# led-er-v2.net
KiCad netlist of a schematic drawn in EAGLE
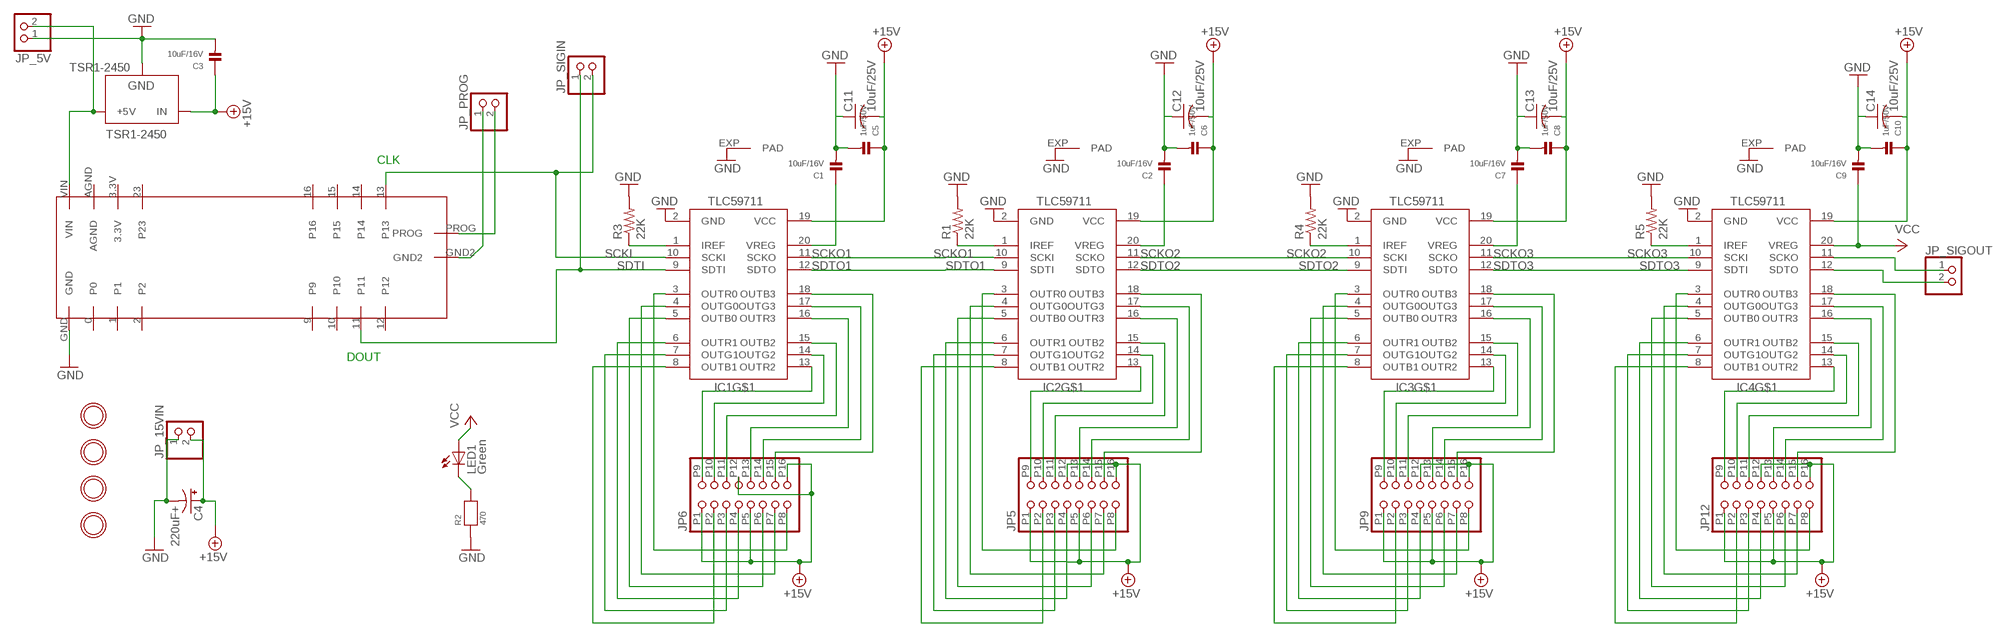
[diagram p0: schematic, sheet 1]

(export (version "E")
  (design (tool "Eeschema 10.0.6"))
  (components
    (comp (ref "C1")
      (value "10uF/16V")
      (footprint "eagle-import:0805")
      (libsource (lib "eagle-import") (part "CAP_CERAMIC0805"))
    )
    (comp (ref "C2")
      (value "10uF/16V")
      (footprint "eagle-import:0805")
      (libsource (lib "eagle-import") (part "CAP_CERAMIC0805"))
    )
    (comp (ref "C3")
      (value "10uF/16V")
      (footprint "eagle-import:0805")
      (libsource (lib "eagle-import") (part "CAP_CERAMIC0805"))
    )
    (comp (ref "C4")
      (value "220uF+")
      (footprint "eagle-import:E5-8,5")
      (libsource (lib "eagle-import") (part "CPOL-USE5-8.5"))
    )
    (comp (ref "C5")
      (value "1uF/50V")
      (footprint "eagle-import:0805")
      (libsource (lib "eagle-import") (part "CAP_CERAMIC0805"))
    )
    (comp (ref "C6")
      (value "1uF/50V")
      (footprint "eagle-import:0805")
      (libsource (lib "eagle-import") (part "CAP_CERAMIC0805"))
    )
    (comp (ref "C7")
      (value "10uF/16V")
      (footprint "eagle-import:0805")
      (libsource (lib "eagle-import") (part "CAP_CERAMIC0805"))
    )
    (comp (ref "C8")
      (value "1uF/50V")
      (footprint "eagle-import:0805")
      (libsource (lib "eagle-import") (part "CAP_CERAMIC0805"))
    )
    (comp (ref "C9")
      (value "10uF/16V")
      (footprint "eagle-import:0805")
      (libsource (lib "eagle-import") (part "CAP_CERAMIC0805"))
    )
    (comp (ref "C10")
      (value "1uF/50V")
      (footprint "eagle-import:0805")
      (libsource (lib "eagle-import") (part "CAP_CERAMIC0805"))
    )
    (comp (ref "C11")
      (value "10uF/25V")
      (footprint "eagle-import:C0805")
      (libsource (lib "eagle-import") (part "C-USC0805"))
    )
    (comp (ref "C12")
      (value "10uF/25V")
      (footprint "eagle-import:C0805")
      (libsource (lib "eagle-import") (part "C-USC0805"))
    )
    (comp (ref "C13")
      (value "10uF/25V")
      (footprint "eagle-import:C0805")
      (libsource (lib "eagle-import") (part "C-USC0805"))
    )
    (comp (ref "C14")
      (value "10uF/25V")
      (footprint "eagle-import:C0805")
      (libsource (lib "eagle-import") (part "C-USC0805"))
    )
    (comp (ref "IC1")
      (value "TLC59711")
      (footprint "eagle-import:HTSSOP20DAP")
      (libsource (lib "eagle-import") (part "TLC59711"))
    )
    (comp (ref "IC2")
      (value "TLC59711")
      (footprint "eagle-import:HTSSOP20DAP")
      (libsource (lib "eagle-import") (part "TLC59711"))
    )
    (comp (ref "IC3")
      (value "TLC59711")
      (footprint "eagle-import:HTSSOP20DAP")
      (libsource (lib "eagle-import") (part "TLC59711"))
    )
    (comp (ref "IC4")
      (value "TLC59711")
      (footprint "eagle-import:HTSSOP20DAP")
      (libsource (lib "eagle-import") (part "TLC59711"))
    )
    (comp (ref "JP5")
      (value "HEADER-2X8")
      (footprint "eagle-import:2X08")
      (libsource (lib "eagle-import") (part "HEADER-2X8"))
    )
    (comp (ref "JP6")
      (value "HEADER-2X8")
      (footprint "eagle-import:2X08")
      (libsource (lib "eagle-import") (part "HEADER-2X8"))
    )
    (comp (ref "JP9")
      (value "HEADER-2X8")
      (footprint "eagle-import:2X08")
      (libsource (lib "eagle-import") (part "HEADER-2X8"))
    )
    (comp (ref "JP12")
      (value "HEADER-2X8")
      (footprint "eagle-import:2X08")
      (libsource (lib "eagle-import") (part "HEADER-2X8"))
    )
    (comp (ref "JP_5V")
      (value "HEADER-1X2")
      (footprint "eagle-import:1X02_OVAL")
      (libsource (lib "eagle-import") (part "HEADER-1X2"))
    )
    (comp (ref "JP_15VIN")
      (value "HEADER-1X2")
      (footprint "eagle-import:1X02_OVAL")
      (libsource (lib "eagle-import") (part "HEADER-1X2"))
    )
    (comp (ref "JP_PROG")
      (value "HEADER-1X2")
      (footprint "eagle-import:1X02_OVAL")
      (libsource (lib "eagle-import") (part "HEADER-1X2"))
    )
    (comp (ref "JP_SIGIN")
      (value "HEADER-1X2")
      (footprint "eagle-import:1X02_OVAL")
      (libsource (lib "eagle-import") (part "HEADER-1X2"))
    )
    (comp (ref "JP_SIGOUT")
      (value "HEADER-1X2")
      (footprint "eagle-import:1X02_OVAL")
      (libsource (lib "eagle-import") (part "HEADER-1X2"))
    )
    (comp (ref "LED1")
      (value "Green")
      (footprint "eagle-import:CHIP-LED0805")
      (libsource (lib "eagle-import") (part "LEDCHIP-LED0805"))
    )
    (comp (ref "R1")
      (value "22K")
      (footprint "eagle-import:0805-THM-7")
      (libsource (lib "eagle-import") (part "R-US_FLIPFLOP7"))
    )
    (comp (ref "R2")
      (value "470")
      (footprint "eagle-import:0805")
      (libsource (lib "eagle-import") (part "RESISTOR0805"))
    )
    (comp (ref "R3")
      (value "22K")
      (footprint "eagle-import:0805-THM-7")
      (libsource (lib "eagle-import") (part "R-US_FLIPFLOP7"))
    )
    (comp (ref "R4")
      (value "22K")
      (footprint "eagle-import:0805-THM-7")
      (libsource (lib "eagle-import") (part "R-US_FLIPFLOP7"))
    )
    (comp (ref "R5")
      (value "22K")
      (footprint "eagle-import:0805-THM-7")
      (libsource (lib "eagle-import") (part "R-US_FLIPFLOP7"))
    )
    (comp (ref "TSR1-2450")
      (value "TSR1-2450")
      (footprint "eagle-import:TSR-1")
      (libsource (lib "eagle-import") (part "TSR1-2450"))
    )
    (comp (ref "U$1")
      (value "MOUNTINGHOLE")
      (footprint "eagle-import:MOUNTINGHOLE_3.0_PLATED")
      (libsource (lib "eagle-import") (part "MOUNTINGHOLE"))
    )
    (comp (ref "U$2")
      (value "MOUNTINGHOLE")
      (footprint "eagle-import:MOUNTINGHOLE_3.0_PLATED")
      (libsource (lib "eagle-import") (part "MOUNTINGHOLE"))
    )
    (comp (ref "U$3")
      (value "MOUNTINGHOLE")
      (footprint "eagle-import:MOUNTINGHOLE_3.0_PLATED")
      (libsource (lib "eagle-import") (part "MOUNTINGHOLE"))
    )
    (comp (ref "U$4")
      (value "MOUNTINGHOLE")
      (footprint "eagle-import:MOUNTINGHOLE_3.0_PLATED")
      (libsource (lib "eagle-import") (part "MOUNTINGHOLE"))
    )
    (comp (ref "U$5")
      (value "TEENSY_LEDER")
      (footprint "eagle-import:TEENSY_LEDER")
      (libsource (lib "eagle-import") (part "TEENSY_LEDER"))
    )
  )
  (nets
    (net (code "1") (name "+15V") (class "Default")
      (node (ref "C10") (pin "1") (pinfunction "P$1_1") (pintype "passive"))
      (node (ref "C11") (pin "2") (pinfunction "2_2") (pintype "passive"))
      (node (ref "C12") (pin "2") (pinfunction "2_2") (pintype "passive"))
      (node (ref "C13") (pin "2") (pinfunction "2_2") (pintype "passive"))
      (node (ref "C14") (pin "2") (pinfunction "2_2") (pintype "passive"))
      (node (ref "C3") (pin "1") (pinfunction "P$1_1") (pintype "passive"))
      (node (ref "C4") (pin "+") (pinfunction "+_+") (pintype "passive"))
      (node (ref "C5") (pin "1") (pinfunction "P$1_1") (pintype "passive"))
      (node (ref "C6") (pin "1") (pinfunction "P$1_1") (pintype "passive"))
      (node (ref "C8") (pin "1") (pinfunction "P$1_1") (pintype "passive"))
      (node (ref "IC1") (pin "19") (pinfunction "VCC_19") (pintype "power_in"))
      (node (ref "IC2") (pin "19") (pinfunction "VCC_19") (pintype "power_in"))
      (node (ref "IC3") (pin "19") (pinfunction "VCC_19") (pintype "power_in"))
      (node (ref "IC4") (pin "19") (pinfunction "VCC_19") (pintype "power_in"))
      (node (ref "JP12") (pin "P1") (pinfunction "P1_P1") (pintype "passive"))
      (node (ref "JP12") (pin "P12") (pinfunction "P12_P12") (pintype "passive"))
      (node (ref "JP12") (pin "P16") (pinfunction "P16_P16") (pintype "passive"))
      (node (ref "JP12") (pin "P5") (pinfunction "P5_P5") (pintype "passive"))
      (node (ref "JP5") (pin "P1") (pinfunction "P1_P1") (pintype "passive"))
      (node (ref "JP5") (pin "P12") (pinfunction "P12_P12") (pintype "passive"))
      (node (ref "JP5") (pin "P16") (pinfunction "P16_P16") (pintype "passive"))
      (node (ref "JP5") (pin "P5") (pinfunction "P5_P5") (pintype "passive"))
      (node (ref "JP6") (pin "P1") (pinfunction "P1_P1") (pintype "passive"))
      (node (ref "JP6") (pin "P12") (pinfunction "P12_P12") (pintype "passive"))
      (node (ref "JP6") (pin "P16") (pinfunction "P16_P16") (pintype "passive"))
      (node (ref "JP6") (pin "P5") (pinfunction "P5_P5") (pintype "passive"))
      (node (ref "JP9") (pin "P1") (pinfunction "P1_P1") (pintype "passive"))
      (node (ref "JP9") (pin "P12") (pinfunction "P12_P12") (pintype "passive"))
      (node (ref "JP9") (pin "P16") (pinfunction "P16_P16") (pintype "passive"))
      (node (ref "JP9") (pin "P5") (pinfunction "P5_P5") (pintype "passive"))
      (node (ref "JP_15VIN") (pin "2") (pinfunction "2_2") (pintype "passive"))
      (node (ref "TSR1-2450") (pin "1") (pinfunction "IN_1") (pintype "power_in"))
    )
    (net (code "2") (name "/SCKI") (class "Default")
      (node (ref "IC1") (pin "10") (pinfunction "SCKI_10") (pintype "input"))
      (node (ref "JP_SIGIN") (pin "2") (pinfunction "2_2") (pintype "passive"))
      (node (ref "U$5") (pin "13") (pinfunction "P13_13") (pintype "bidirectional"))
    )
    (net (code "3") (name "/SCKO1") (class "Default")
      (node (ref "IC1") (pin "11") (pinfunction "SCKO_11") (pintype "output"))
      (node (ref "IC2") (pin "10") (pinfunction "SCKI_10") (pintype "input"))
    )
    (net (code "4") (name "/SCKO2") (class "Default")
      (node (ref "IC2") (pin "11") (pinfunction "SCKO_11") (pintype "output"))
      (node (ref "IC3") (pin "10") (pinfunction "SCKI_10") (pintype "input"))
    )
    (net (code "5") (name "/SCKO3") (class "Default")
      (node (ref "IC3") (pin "11") (pinfunction "SCKO_11") (pintype "output"))
      (node (ref "IC4") (pin "10") (pinfunction "SCKI_10") (pintype "input"))
    )
    (net (code "6") (name "/SDTI") (class "Default")
      (node (ref "IC1") (pin "9") (pinfunction "SDTI_9") (pintype "input"))
      (node (ref "JP_SIGIN") (pin "1") (pinfunction "1_1") (pintype "passive"))
      (node (ref "U$5") (pin "11") (pinfunction "P11_11") (pintype "bidirectional"))
    )
    (net (code "7") (name "/SDTO1") (class "Default")
      (node (ref "IC1") (pin "12") (pinfunction "SDTO_12") (pintype "output"))
      (node (ref "IC2") (pin "9") (pinfunction "SDTI_9") (pintype "input"))
    )
    (net (code "8") (name "/SDTO2") (class "Default")
      (node (ref "IC2") (pin "12") (pinfunction "SDTO_12") (pintype "output"))
      (node (ref "IC3") (pin "9") (pinfunction "SDTI_9") (pintype "input"))
    )
    (net (code "9") (name "/SDTO3") (class "Default")
      (node (ref "IC3") (pin "12") (pinfunction "SDTO_12") (pintype "output"))
      (node (ref "IC4") (pin "9") (pinfunction "SDTI_9") (pintype "input"))
    )
    (net (code "10") (name "GND") (class "Default")
      (node (ref "C1") (pin "2") (pinfunction "P$2_2") (pintype "passive"))
      (node (ref "C10") (pin "2") (pinfunction "P$2_2") (pintype "passive"))
      (node (ref "C11") (pin "1") (pinfunction "1_1") (pintype "passive"))
      (node (ref "C12") (pin "1") (pinfunction "1_1") (pintype "passive"))
      (node (ref "C13") (pin "1") (pinfunction "1_1") (pintype "passive"))
      (node (ref "C14") (pin "1") (pinfunction "1_1") (pintype "passive"))
      (node (ref "C2") (pin "2") (pinfunction "P$2_2") (pintype "passive"))
      (node (ref "C3") (pin "2") (pinfunction "P$2_2") (pintype "passive"))
      (node (ref "C4") (pin "-") (pinfunction "-_-") (pintype "passive"))
      (node (ref "C5") (pin "2") (pinfunction "P$2_2") (pintype "passive"))
      (node (ref "C6") (pin "2") (pinfunction "P$2_2") (pintype "passive"))
      (node (ref "C7") (pin "2") (pinfunction "P$2_2") (pintype "passive"))
      (node (ref "C8") (pin "2") (pinfunction "P$2_2") (pintype "passive"))
      (node (ref "C9") (pin "2") (pinfunction "P$2_2") (pintype "passive"))
      (node (ref "IC1") (pin "2") (pinfunction "GND_2") (pintype "power_in"))
      (node (ref "IC1") (pin "EXP") (pinfunction "PAD_EXP") (pintype "passive"))
      (node (ref "IC2") (pin "2") (pinfunction "GND_2") (pintype "power_in"))
      (node (ref "IC2") (pin "EXP") (pinfunction "PAD_EXP") (pintype "passive"))
      (node (ref "IC3") (pin "2") (pinfunction "GND_2") (pintype "power_in"))
      (node (ref "IC3") (pin "EXP") (pinfunction "PAD_EXP") (pintype "passive"))
      (node (ref "IC4") (pin "2") (pinfunction "GND_2") (pintype "power_in"))
      (node (ref "IC4") (pin "EXP") (pinfunction "PAD_EXP") (pintype "passive"))
      (node (ref "JP_15VIN") (pin "1") (pinfunction "1_1") (pintype "passive"))
      (node (ref "JP_5V") (pin "1") (pinfunction "1_1") (pintype "passive"))
      (node (ref "R1") (pin "2") (pinfunction "2_2") (pintype "passive"))
      (node (ref "R2") (pin "1") (pinfunction "1_1") (pintype "passive"))
      (node (ref "R3") (pin "2") (pinfunction "2_2") (pintype "passive"))
      (node (ref "R4") (pin "2") (pinfunction "2_2") (pintype "passive"))
      (node (ref "R5") (pin "2") (pinfunction "2_2") (pintype "passive"))
      (node (ref "TSR1-2450") (pin "2") (pinfunction "GND_2") (pintype "power_in"))
      (node (ref "U$5") (pin "GND") (pinfunction "GND_GND") (pintype "bidirectional"))
    )
    (net (code "11") (name "Net-(C1-P$1)") (class "Default")
      (node (ref "C1") (pin "1") (pinfunction "P$1_1") (pintype "passive"))
      (node (ref "IC1") (pin "20") (pinfunction "VREG_20") (pintype "bidirectional"))
    )
    (net (code "12") (name "Net-(C2-P$1)") (class "Default")
      (node (ref "C2") (pin "1") (pinfunction "P$1_1") (pintype "passive"))
      (node (ref "IC2") (pin "20") (pinfunction "VREG_20") (pintype "bidirectional"))
    )
    (net (code "13") (name "Net-(C7-P$1)") (class "Default")
      (node (ref "C7") (pin "1") (pinfunction "P$1_1") (pintype "passive"))
      (node (ref "IC3") (pin "20") (pinfunction "VREG_20") (pintype "bidirectional"))
    )
    (net (code "14") (name "Net-(IC1A-IREF)") (class "Default")
      (node (ref "IC1") (pin "1") (pinfunction "IREF_1") (pintype "bidirectional"))
      (node (ref "R3") (pin "1") (pinfunction "1_1") (pintype "passive"))
    )
    (net (code "15") (name "Net-(IC1A-OUTB0)") (class "Default")
      (node (ref "IC1") (pin "5") (pinfunction "OUTB0_5") (pintype "open_collector"))
      (node (ref "JP6") (pin "P6") (pinfunction "P6_P6") (pintype "passive"))
    )
    (net (code "16") (name "Net-(IC1A-OUTB1)") (class "Default")
      (node (ref "IC1") (pin "8") (pinfunction "OUTB1_8") (pintype "open_collector"))
      (node (ref "JP6") (pin "P2") (pinfunction "P2_P2") (pintype "passive"))
    )
    (net (code "17") (name "Net-(IC1A-OUTB2)") (class "Default")
      (node (ref "IC1") (pin "15") (pinfunction "OUTB2_15") (pintype "open_collector"))
      (node (ref "JP6") (pin "P11") (pinfunction "P11_P11") (pintype "passive"))
    )
    (net (code "18") (name "Net-(IC1A-OUTB3)") (class "Default")
      (node (ref "IC1") (pin "18") (pinfunction "OUTB3_18") (pintype "open_collector"))
      (node (ref "JP6") (pin "P15") (pinfunction "P15_P15") (pintype "passive"))
    )
    (net (code "19") (name "Net-(IC1A-OUTG0)") (class "Default")
      (node (ref "IC1") (pin "4") (pinfunction "OUTG0_4") (pintype "open_collector"))
      (node (ref "JP6") (pin "P7") (pinfunction "P7_P7") (pintype "passive"))
    )
    (net (code "20") (name "Net-(IC1A-OUTG1)") (class "Default")
      (node (ref "IC1") (pin "7") (pinfunction "OUTG1_7") (pintype "open_collector"))
      (node (ref "JP6") (pin "P3") (pinfunction "P3_P3") (pintype "passive"))
    )
    (net (code "21") (name "Net-(IC1A-OUTG2)") (class "Default")
      (node (ref "IC1") (pin "14") (pinfunction "OUTG2_14") (pintype "open_collector"))
      (node (ref "JP6") (pin "P10") (pinfunction "P10_P10") (pintype "passive"))
    )
    (net (code "22") (name "Net-(IC1A-OUTG3)") (class "Default")
      (node (ref "IC1") (pin "17") (pinfunction "OUTG3_17") (pintype "open_collector"))
      (node (ref "JP6") (pin "P14") (pinfunction "P14_P14") (pintype "passive"))
    )
    (net (code "23") (name "Net-(IC1A-OUTR0)") (class "Default")
      (node (ref "IC1") (pin "3") (pinfunction "OUTR0_3") (pintype "open_collector"))
      (node (ref "JP6") (pin "P8") (pinfunction "P8_P8") (pintype "passive"))
    )
    (net (code "24") (name "Net-(IC1A-OUTR1)") (class "Default")
      (node (ref "IC1") (pin "6") (pinfunction "OUTR1_6") (pintype "open_collector"))
      (node (ref "JP6") (pin "P4") (pinfunction "P4_P4") (pintype "passive"))
    )
    (net (code "25") (name "Net-(IC1A-OUTR2)") (class "Default")
      (node (ref "IC1") (pin "13") (pinfunction "OUTR2_13") (pintype "open_collector"))
      (node (ref "JP6") (pin "P9") (pinfunction "P9_P9") (pintype "passive"))
    )
    (net (code "26") (name "Net-(IC1A-OUTR3)") (class "Default")
      (node (ref "IC1") (pin "16") (pinfunction "OUTR3_16") (pintype "open_collector"))
      (node (ref "JP6") (pin "P13") (pinfunction "P13_P13") (pintype "passive"))
    )
    (net (code "27") (name "Net-(IC2A-IREF)") (class "Default")
      (node (ref "IC2") (pin "1") (pinfunction "IREF_1") (pintype "bidirectional"))
      (node (ref "R1") (pin "1") (pinfunction "1_1") (pintype "passive"))
    )
    (net (code "28") (name "Net-(IC2A-OUTB0)") (class "Default")
      (node (ref "IC2") (pin "5") (pinfunction "OUTB0_5") (pintype "open_collector"))
      (node (ref "JP5") (pin "P6") (pinfunction "P6_P6") (pintype "passive"))
    )
    (net (code "29") (name "Net-(IC2A-OUTB1)") (class "Default")
      (node (ref "IC2") (pin "8") (pinfunction "OUTB1_8") (pintype "open_collector"))
      (node (ref "JP5") (pin "P2") (pinfunction "P2_P2") (pintype "passive"))
    )
    (net (code "30") (name "Net-(IC2A-OUTB2)") (class "Default")
      (node (ref "IC2") (pin "15") (pinfunction "OUTB2_15") (pintype "open_collector"))
      (node (ref "JP5") (pin "P11") (pinfunction "P11_P11") (pintype "passive"))
    )
    (net (code "31") (name "Net-(IC2A-OUTB3)") (class "Default")
      (node (ref "IC2") (pin "18") (pinfunction "OUTB3_18") (pintype "open_collector"))
      (node (ref "JP5") (pin "P15") (pinfunction "P15_P15") (pintype "passive"))
    )
    (net (code "32") (name "Net-(IC2A-OUTG0)") (class "Default")
      (node (ref "IC2") (pin "4") (pinfunction "OUTG0_4") (pintype "open_collector"))
      (node (ref "JP5") (pin "P7") (pinfunction "P7_P7") (pintype "passive"))
    )
    (net (code "33") (name "Net-(IC2A-OUTG1)") (class "Default")
      (node (ref "IC2") (pin "7") (pinfunction "OUTG1_7") (pintype "open_collector"))
      (node (ref "JP5") (pin "P3") (pinfunction "P3_P3") (pintype "passive"))
    )
    (net (code "34") (name "Net-(IC2A-OUTG2)") (class "Default")
      (node (ref "IC2") (pin "14") (pinfunction "OUTG2_14") (pintype "open_collector"))
      (node (ref "JP5") (pin "P10") (pinfunction "P10_P10") (pintype "passive"))
    )
    (net (code "35") (name "Net-(IC2A-OUTG3)") (class "Default")
      (node (ref "IC2") (pin "17") (pinfunction "OUTG3_17") (pintype "open_collector"))
      (node (ref "JP5") (pin "P14") (pinfunction "P14_P14") (pintype "passive"))
    )
    (net (code "36") (name "Net-(IC2A-OUTR0)") (class "Default")
      (node (ref "IC2") (pin "3") (pinfunction "OUTR0_3") (pintype "open_collector"))
      (node (ref "JP5") (pin "P8") (pinfunction "P8_P8") (pintype "passive"))
    )
    (net (code "37") (name "Net-(IC2A-OUTR1)") (class "Default")
      (node (ref "IC2") (pin "6") (pinfunction "OUTR1_6") (pintype "open_collector"))
      (node (ref "JP5") (pin "P4") (pinfunction "P4_P4") (pintype "passive"))
    )
    (net (code "38") (name "Net-(IC2A-OUTR2)") (class "Default")
      (node (ref "IC2") (pin "13") (pinfunction "OUTR2_13") (pintype "open_collector"))
      (node (ref "JP5") (pin "P9") (pinfunction "P9_P9") (pintype "passive"))
    )
    (net (code "39") (name "Net-(IC2A-OUTR3)") (class "Default")
      (node (ref "IC2") (pin "16") (pinfunction "OUTR3_16") (pintype "open_collector"))
      (node (ref "JP5") (pin "P13") (pinfunction "P13_P13") (pintype "passive"))
    )
    (net (code "40") (name "Net-(IC3A-IREF)") (class "Default")
      (node (ref "IC3") (pin "1") (pinfunction "IREF_1") (pintype "bidirectional"))
      (node (ref "R4") (pin "1") (pinfunction "1_1") (pintype "passive"))
    )
    (net (code "41") (name "Net-(IC3A-OUTB0)") (class "Default")
      (node (ref "IC3") (pin "5") (pinfunction "OUTB0_5") (pintype "open_collector"))
      (node (ref "JP9") (pin "P6") (pinfunction "P6_P6") (pintype "passive"))
    )
    (net (code "42") (name "Net-(IC3A-OUTB1)") (class "Default")
      (node (ref "IC3") (pin "8") (pinfunction "OUTB1_8") (pintype "open_collector"))
      (node (ref "JP9") (pin "P2") (pinfunction "P2_P2") (pintype "passive"))
    )
    (net (code "43") (name "Net-(IC3A-OUTB2)") (class "Default")
      (node (ref "IC3") (pin "15") (pinfunction "OUTB2_15") (pintype "open_collector"))
      (node (ref "JP9") (pin "P11") (pinfunction "P11_P11") (pintype "passive"))
    )
    (net (code "44") (name "Net-(IC3A-OUTB3)") (class "Default")
      (node (ref "IC3") (pin "18") (pinfunction "OUTB3_18") (pintype "open_collector"))
      (node (ref "JP9") (pin "P15") (pinfunction "P15_P15") (pintype "passive"))
    )
    (net (code "45") (name "Net-(IC3A-OUTG0)") (class "Default")
      (node (ref "IC3") (pin "4") (pinfunction "OUTG0_4") (pintype "open_collector"))
      (node (ref "JP9") (pin "P7") (pinfunction "P7_P7") (pintype "passive"))
    )
    (net (code "46") (name "Net-(IC3A-OUTG1)") (class "Default")
      (node (ref "IC3") (pin "7") (pinfunction "OUTG1_7") (pintype "open_collector"))
      (node (ref "JP9") (pin "P3") (pinfunction "P3_P3") (pintype "passive"))
    )
    (net (code "47") (name "Net-(IC3A-OUTG2)") (class "Default")
      (node (ref "IC3") (pin "14") (pinfunction "OUTG2_14") (pintype "open_collector"))
      (node (ref "JP9") (pin "P10") (pinfunction "P10_P10") (pintype "passive"))
    )
    (net (code "48") (name "Net-(IC3A-OUTG3)") (class "Default")
      (node (ref "IC3") (pin "17") (pinfunction "OUTG3_17") (pintype "open_collector"))
      (node (ref "JP9") (pin "P14") (pinfunction "P14_P14") (pintype "passive"))
    )
    (net (code "49") (name "Net-(IC3A-OUTR0)") (class "Default")
      (node (ref "IC3") (pin "3") (pinfunction "OUTR0_3") (pintype "open_collector"))
      (node (ref "JP9") (pin "P8") (pinfunction "P8_P8") (pintype "passive"))
    )
    (net (code "50") (name "Net-(IC3A-OUTR1)") (class "Default")
      (node (ref "IC3") (pin "6") (pinfunction "OUTR1_6") (pintype "open_collector"))
      (node (ref "JP9") (pin "P4") (pinfunction "P4_P4") (pintype "passive"))
    )
    (net (code "51") (name "Net-(IC3A-OUTR2)") (class "Default")
      (node (ref "IC3") (pin "13") (pinfunction "OUTR2_13") (pintype "open_collector"))
      (node (ref "JP9") (pin "P9") (pinfunction "P9_P9") (pintype "passive"))
    )
    (net (code "52") (name "Net-(IC3A-OUTR3)") (class "Default")
      (node (ref "IC3") (pin "16") (pinfunction "OUTR3_16") (pintype "open_collector"))
      (node (ref "JP9") (pin "P13") (pinfunction "P13_P13") (pintype "passive"))
    )
    (net (code "53") (name "Net-(IC4A-IREF)") (class "Default")
      (node (ref "IC4") (pin "1") (pinfunction "IREF_1") (pintype "bidirectional"))
      (node (ref "R5") (pin "1") (pinfunction "1_1") (pintype "passive"))
    )
    (net (code "54") (name "Net-(IC4A-OUTB0)") (class "Default")
      (node (ref "IC4") (pin "5") (pinfunction "OUTB0_5") (pintype "open_collector"))
      (node (ref "JP12") (pin "P6") (pinfunction "P6_P6") (pintype "passive"))
    )
    (net (code "55") (name "Net-(IC4A-OUTB1)") (class "Default")
      (node (ref "IC4") (pin "8") (pinfunction "OUTB1_8") (pintype "open_collector"))
      (node (ref "JP12") (pin "P2") (pinfunction "P2_P2") (pintype "passive"))
    )
    (net (code "56") (name "Net-(IC4A-OUTB2)") (class "Default")
      (node (ref "IC4") (pin "15") (pinfunction "OUTB2_15") (pintype "open_collector"))
      (node (ref "JP12") (pin "P11") (pinfunction "P11_P11") (pintype "passive"))
    )
    (net (code "57") (name "Net-(IC4A-OUTB3)") (class "Default")
      (node (ref "IC4") (pin "18") (pinfunction "OUTB3_18") (pintype "open_collector"))
      (node (ref "JP12") (pin "P15") (pinfunction "P15_P15") (pintype "passive"))
    )
    (net (code "58") (name "Net-(IC4A-OUTG0)") (class "Default")
      (node (ref "IC4") (pin "4") (pinfunction "OUTG0_4") (pintype "open_collector"))
      (node (ref "JP12") (pin "P7") (pinfunction "P7_P7") (pintype "passive"))
    )
    (net (code "59") (name "Net-(IC4A-OUTG1)") (class "Default")
      (node (ref "IC4") (pin "7") (pinfunction "OUTG1_7") (pintype "open_collector"))
      (node (ref "JP12") (pin "P3") (pinfunction "P3_P3") (pintype "passive"))
    )
    (net (code "60") (name "Net-(IC4A-OUTG2)") (class "Default")
      (node (ref "IC4") (pin "14") (pinfunction "OUTG2_14") (pintype "open_collector"))
      (node (ref "JP12") (pin "P10") (pinfunction "P10_P10") (pintype "passive"))
    )
    (net (code "61") (name "Net-(IC4A-OUTG3)") (class "Default")
      (node (ref "IC4") (pin "17") (pinfunction "OUTG3_17") (pintype "open_collector"))
      (node (ref "JP12") (pin "P14") (pinfunction "P14_P14") (pintype "passive"))
    )
    (net (code "62") (name "Net-(IC4A-OUTR0)") (class "Default")
      (node (ref "IC4") (pin "3") (pinfunction "OUTR0_3") (pintype "open_collector"))
      (node (ref "JP12") (pin "P8") (pinfunction "P8_P8") (pintype "passive"))
    )
    (net (code "63") (name "Net-(IC4A-OUTR1)") (class "Default")
      (node (ref "IC4") (pin "6") (pinfunction "OUTR1_6") (pintype "open_collector"))
      (node (ref "JP12") (pin "P4") (pinfunction "P4_P4") (pintype "passive"))
    )
    (net (code "64") (name "Net-(IC4A-OUTR2)") (class "Default")
      (node (ref "IC4") (pin "13") (pinfunction "OUTR2_13") (pintype "open_collector"))
      (node (ref "JP12") (pin "P9") (pinfunction "P9_P9") (pintype "passive"))
    )
    (net (code "65") (name "Net-(IC4A-OUTR3)") (class "Default")
      (node (ref "IC4") (pin "16") (pinfunction "OUTR3_16") (pintype "open_collector"))
      (node (ref "JP12") (pin "P13") (pinfunction "P13_P13") (pintype "passive"))
    )
    (net (code "66") (name "Net-(IC4A-SCKO)") (class "Default")
      (node (ref "IC4") (pin "11") (pinfunction "SCKO_11") (pintype "output"))
      (node (ref "JP_SIGOUT") (pin "1") (pinfunction "1_1") (pintype "passive"))
    )
    (net (code "67") (name "Net-(IC4A-SDTO)") (class "Default")
      (node (ref "IC4") (pin "12") (pinfunction "SDTO_12") (pintype "output"))
      (node (ref "JP_SIGOUT") (pin "2") (pinfunction "2_2") (pintype "passive"))
    )
    (net (code "68") (name "Net-(JP_PROG-Pad1)") (class "Default")
      (node (ref "JP_PROG") (pin "1") (pinfunction "1_1") (pintype "passive"))
      (node (ref "U$5") (pin "GND2") (pinfunction "GND2_GND2") (pintype "bidirectional"))
    )
    (net (code "69") (name "Net-(JP_PROG-Pad2)") (class "Default")
      (node (ref "JP_PROG") (pin "2") (pinfunction "2_2") (pintype "passive"))
      (node (ref "U$5") (pin "PROG") (pinfunction "PROG_PROG") (pintype "bidirectional"))
    )
    (net (code "70") (name "Net-(LED1-PadC)") (class "Default")
      (node (ref "LED1") (pin "C") (pinfunction "C_C") (pintype "passive"))
      (node (ref "R2") (pin "2") (pinfunction "2_2") (pintype "passive"))
    )
    (net (code "71") (name "Net-(TSR1-2450-+5V)") (class "Default")
      (node (ref "JP_5V") (pin "2") (pinfunction "2_2") (pintype "passive"))
      (node (ref "TSR1-2450") (pin "3") (pinfunction "+5V_3") (pintype "power_in"))
      (node (ref "U$5") (pin "VIN") (pinfunction "VIN_VIN") (pintype "bidirectional"))
    )
    (net (code "72") (name "VCC") (class "Default")
      (node (ref "C9") (pin "1") (pinfunction "P$1_1") (pintype "passive"))
      (node (ref "IC4") (pin "20") (pinfunction "VREG_20") (pintype "bidirectional"))
      (node (ref "LED1") (pin "A") (pinfunction "A_A") (pintype "passive"))
    )
    (net (code "73") (name "unconnected-(U$5-P0-Pad0)") (class "Default")
      (node (ref "U$5") (pin "0") (pinfunction "P0_0") (pintype "bidirectional"))
    )
    (net (code "74") (name "unconnected-(U$5-P1-Pad1)") (class "Default")
      (node (ref "U$5") (pin "1") (pinfunction "P1_1") (pintype "bidirectional"))
    )
    (net (code "75") (name "unconnected-(U$5-P2-Pad2)") (class "Default")
      (node (ref "U$5") (pin "2") (pinfunction "P2_2") (pintype "bidirectional"))
    )
    (net (code "76") (name "unconnected-(U$5-P9-Pad9)") (class "Default")
      (node (ref "U$5") (pin "9") (pinfunction "P9_9") (pintype "bidirectional"))
    )
    (net (code "77") (name "unconnected-(U$5-P10-Pad10)") (class "Default")
      (node (ref "U$5") (pin "10") (pinfunction "P10_10") (pintype "bidirectional"))
    )
    (net (code "78") (name "unconnected-(U$5-P12-Pad12)") (class "Default")
      (node (ref "U$5") (pin "12") (pinfunction "P12_12") (pintype "bidirectional"))
    )
    (net (code "79") (name "unconnected-(U$5-P14-Pad14)") (class "Default")
      (node (ref "U$5") (pin "14") (pinfunction "P14_14") (pintype "bidirectional"))
    )
    (net (code "80") (name "unconnected-(U$5-P15-Pad15)") (class "Default")
      (node (ref "U$5") (pin "15") (pinfunction "P15_15") (pintype "bidirectional"))
    )
    (net (code "81") (name "unconnected-(U$5-P16-Pad16)") (class "Default")
      (node (ref "U$5") (pin "16") (pinfunction "P16_16") (pintype "bidirectional"))
    )
    (net (code "82") (name "unconnected-(U$5-P23-Pad23)") (class "Default")
      (node (ref "U$5") (pin "23") (pinfunction "P23_23") (pintype "bidirectional"))
    )
    (net (code "83") (name "unconnected-(U$5-Pad3.3V)") (class "Default")
      (node (ref "U$5") (pin "3.3V") (pinfunction "3.3V_3.3V") (pintype "bidirectional"))
    )
    (net (code "84") (name "unconnected-(U$5-PadAGND)") (class "Default")
      (node (ref "U$5") (pin "AGND") (pinfunction "AGND_AGND") (pintype "bidirectional"))
    )
  )
)
